# KMO_IO_MV2_8.net
KiCad netlist of a schematic drawn in EAGLE
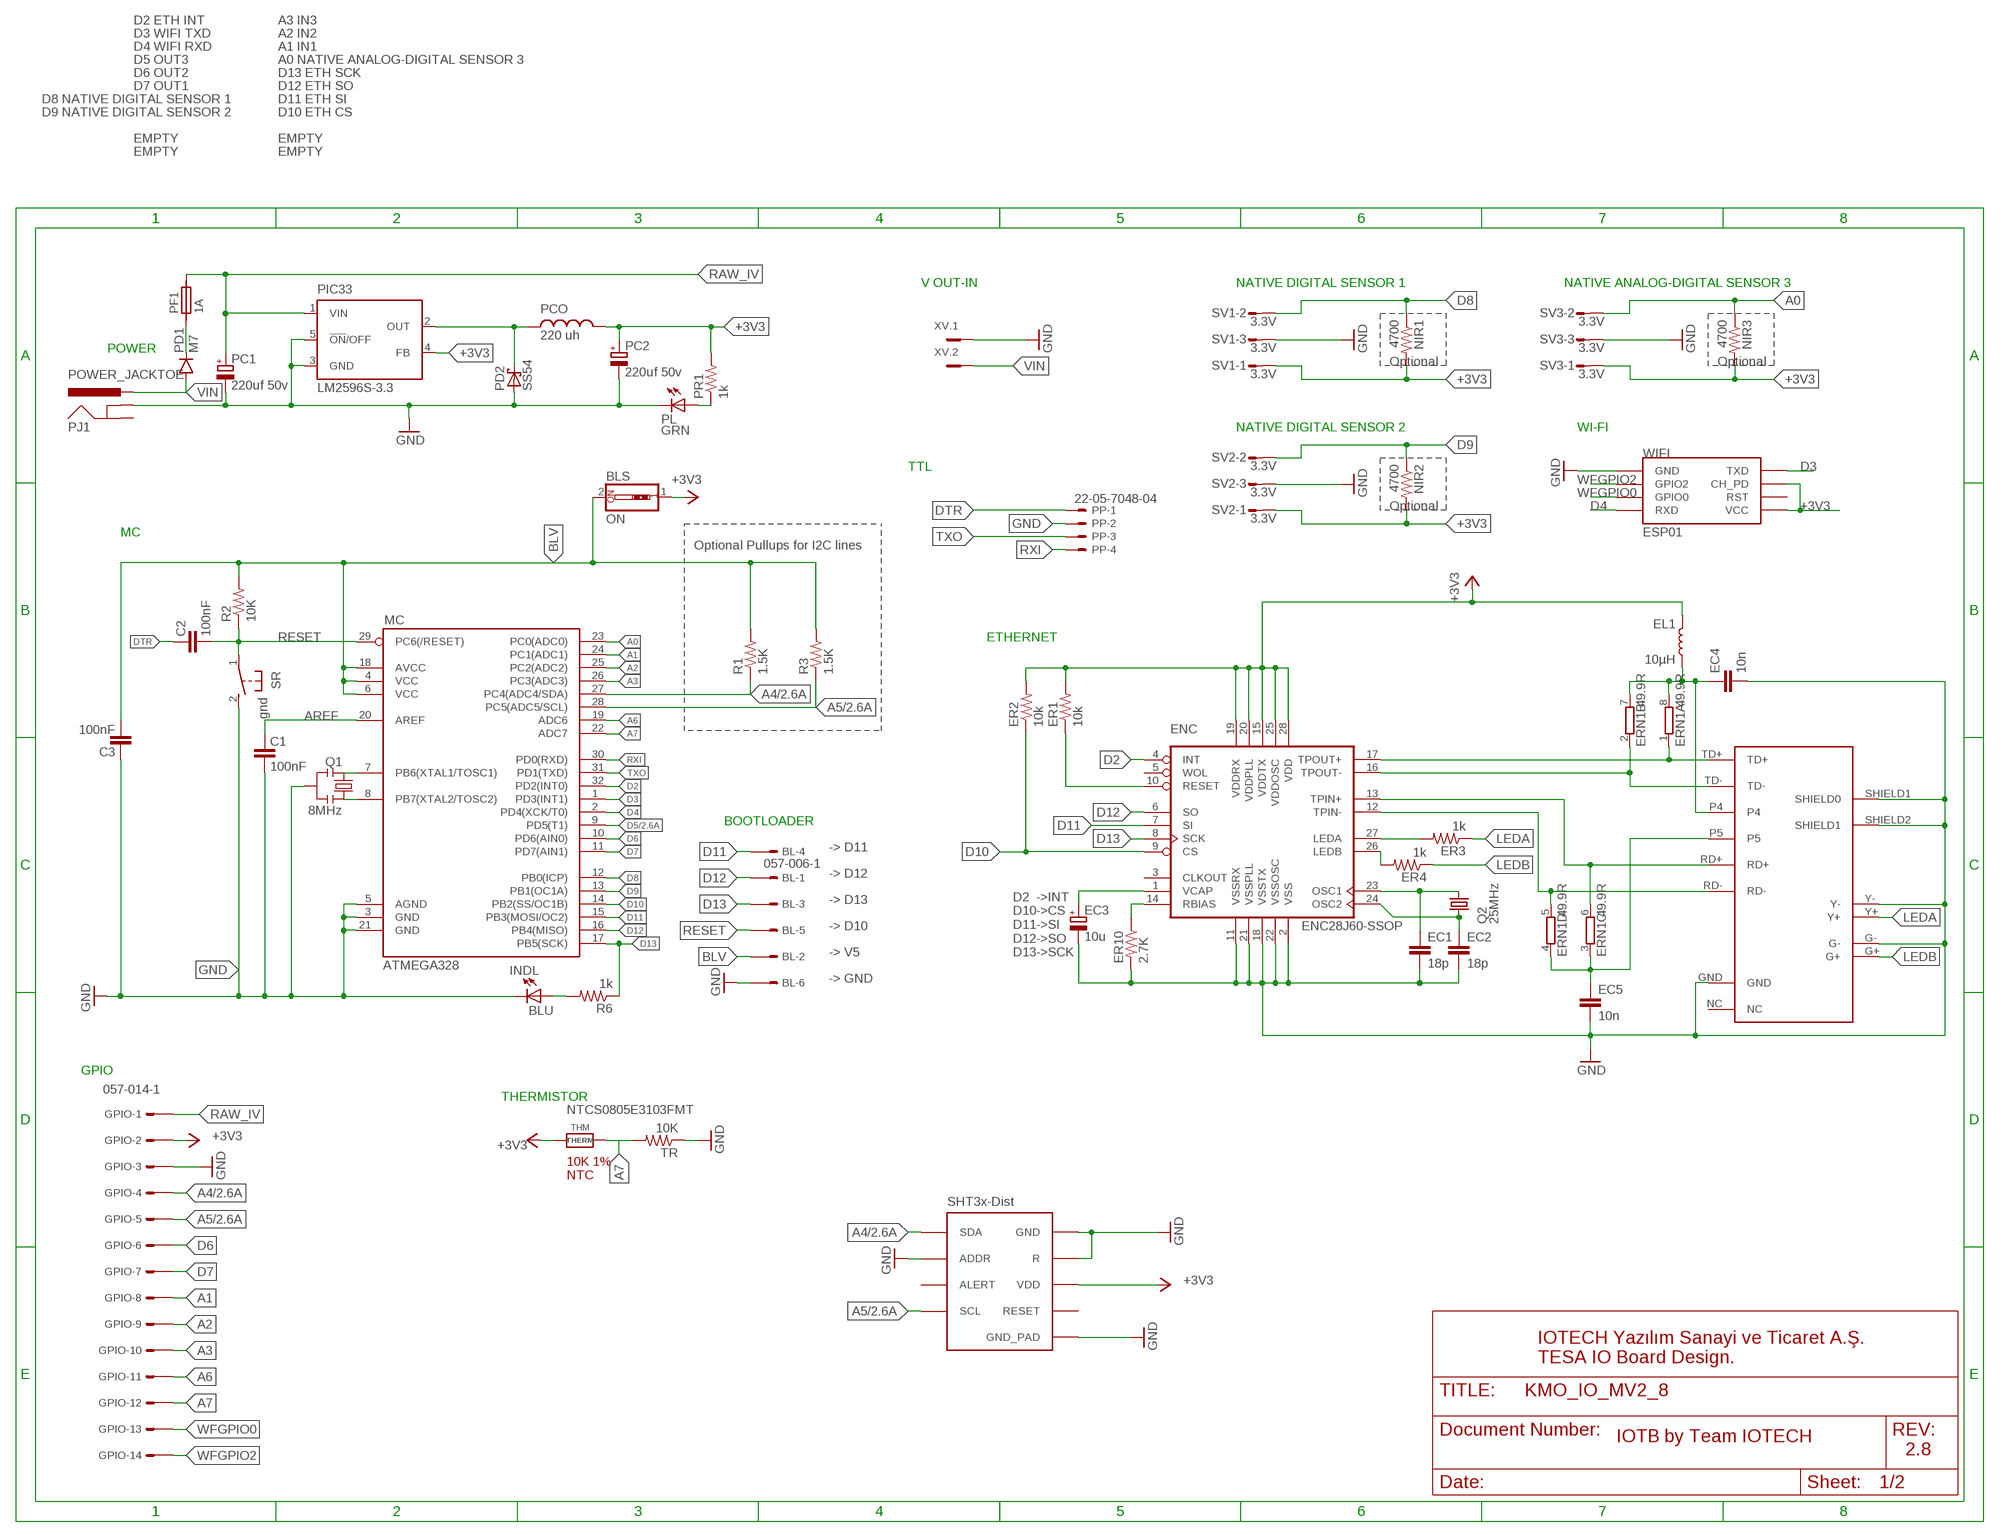
[diagram p0: schematic, sheet 1]
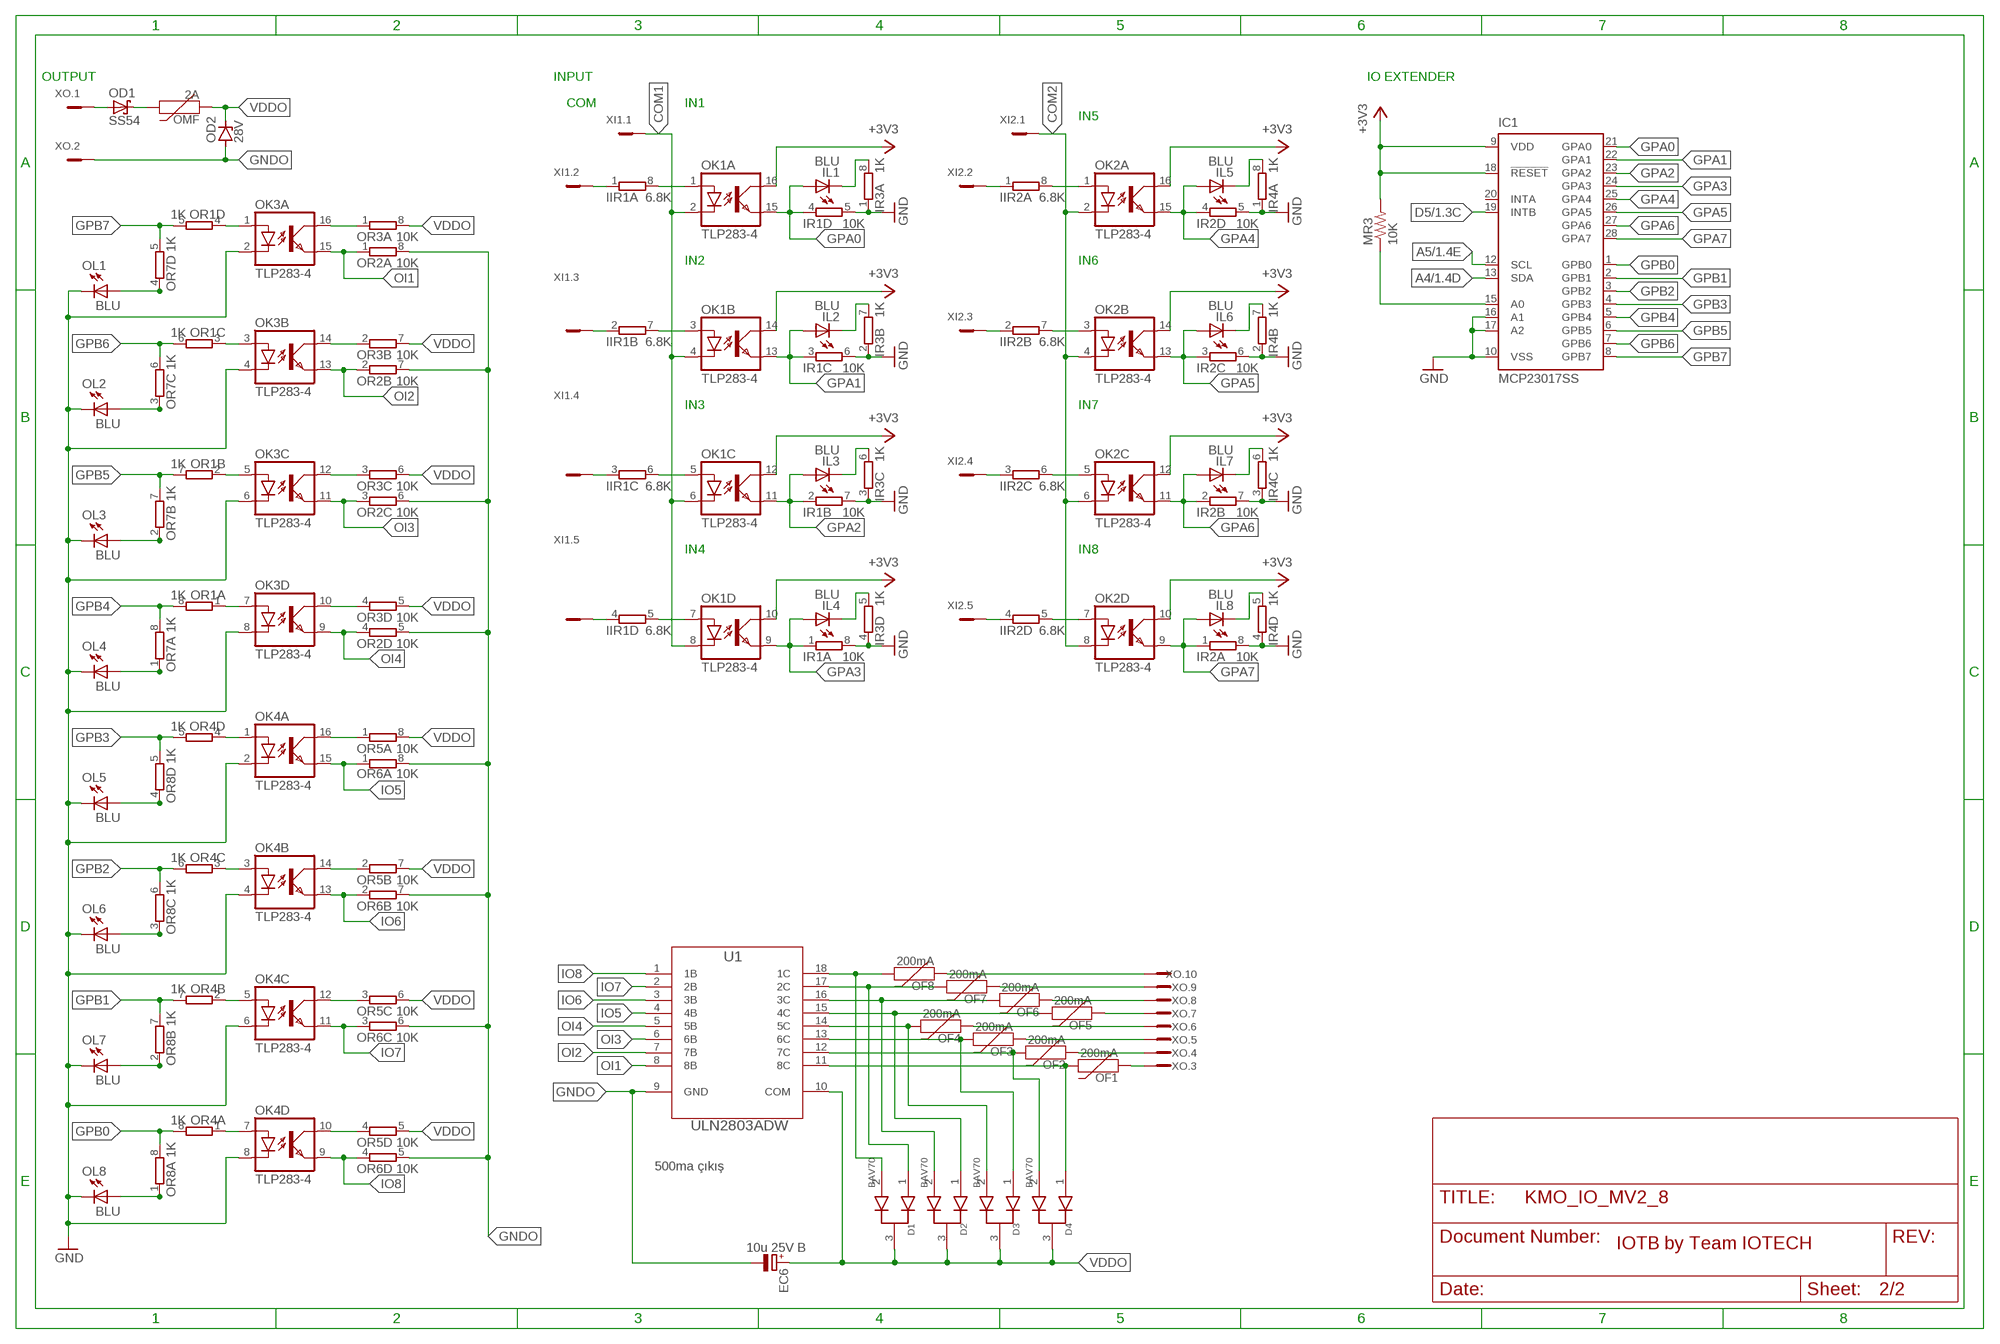
[diagram p1: schematic, sheet 2]

(export (version "E")
  (design (tool "Eeschema 10.0.6"))
  (components
    (comp (ref "D1")
      (value "BAV70")
      (footprint "eagle-import:SOT-23-3")
      (fields (field (name "MF") "Multicomp") (field (name "MP") "BAV70+"))
      (libsource (lib "eagle-import") (part "BAV70"))
    )
    (comp (ref "D2")
      (value "BAV70")
      (footprint "eagle-import:SOT-23-3")
      (fields (field (name "MF") "Multicomp") (field (name "MP") "BAV70+"))
      (libsource (lib "eagle-import") (part "BAV70"))
    )
    (comp (ref "D3")
      (value "BAV70")
      (footprint "eagle-import:SOT-23-3")
      (fields (field (name "MF") "Multicomp") (field (name "MP") "BAV70+"))
      (libsource (lib "eagle-import") (part "BAV70"))
    )
    (comp (ref "D4")
      (value "BAV70")
      (footprint "eagle-import:SOT-23-3")
      (fields (field (name "MF") "Multicomp") (field (name "MP") "BAV70+"))
      (libsource (lib "eagle-import") (part "BAV70"))
    )
    (comp (ref "EC6")
      (value "10u 25V B")
      (footprint "eagle-import:SMC_B")
      (libsource (lib "eagle-import") (part "CPOL-EUSMCB"))
    )
    (comp (ref "IC1")
      (value "MCP23017SS")
      (footprint "eagle-import:SSOP28")
      (fields (field (name "MF") "MICROCHIP") (field (name "MPN") "MCP23017-E/SS"))
      (libsource (lib "eagle-import") (part "MCP23017SS"))
    )
    (comp (ref "IIR1")
      (value "6.8K")
      (footprint "eagle-import:0603-ARV")
      (libsource (lib "eagle-import") (part "4R-N0603-ARV"))
    )
    (comp (ref "IIR2")
      (value "6.8K")
      (footprint "eagle-import:0603-ARV")
      (libsource (lib "eagle-import") (part "4R-N0603-ARV"))
    )
    (comp (ref "IL1")
      (value "BLU")
      (footprint "eagle-import:CHIP-LED0805")
      (libsource (lib "eagle-import") (part "LEDCHIP-LED0805"))
    )
    (comp (ref "IL2")
      (value "BLU")
      (footprint "eagle-import:CHIP-LED0805")
      (libsource (lib "eagle-import") (part "LEDCHIP-LED0805"))
    )
    (comp (ref "IL3")
      (value "BLU")
      (footprint "eagle-import:CHIP-LED0805")
      (libsource (lib "eagle-import") (part "LEDCHIP-LED0805"))
    )
    (comp (ref "IL4")
      (value "BLU")
      (footprint "eagle-import:CHIP-LED0805")
      (libsource (lib "eagle-import") (part "LEDCHIP-LED0805"))
    )
    (comp (ref "IL5")
      (value "BLU")
      (footprint "eagle-import:CHIP-LED0805")
      (libsource (lib "eagle-import") (part "LEDCHIP-LED0805"))
    )
    (comp (ref "IL6")
      (value "BLU")
      (footprint "eagle-import:CHIP-LED0805")
      (libsource (lib "eagle-import") (part "LEDCHIP-LED0805"))
    )
    (comp (ref "IL7")
      (value "BLU")
      (footprint "eagle-import:CHIP-LED0805")
      (libsource (lib "eagle-import") (part "LEDCHIP-LED0805"))
    )
    (comp (ref "IL8")
      (value "BLU")
      (footprint "eagle-import:CHIP-LED0805")
      (libsource (lib "eagle-import") (part "LEDCHIP-LED0805"))
    )
    (comp (ref "IR1")
      (value "10K")
      (footprint "eagle-import:0603-ARV")
      (libsource (lib "eagle-import") (part "4R-N0603-ARV"))
    )
    (comp (ref "IR2")
      (value "10K")
      (footprint "eagle-import:0603-ARV")
      (libsource (lib "eagle-import") (part "4R-N0603-ARV"))
    )
    (comp (ref "IR3")
      (value "1K")
      (footprint "eagle-import:0603-ARV")
      (libsource (lib "eagle-import") (part "4R-N0603-ARV"))
    )
    (comp (ref "IR4")
      (value "1K")
      (footprint "eagle-import:0603-ARV")
      (libsource (lib "eagle-import") (part "4R-N0603-ARV"))
    )
    (comp (ref "MR3")
      (value "10K")
      (footprint "eagle-import:0805")
      (libsource (lib "eagle-import") (part "RESISTOR0805-RES"))
    )
    (comp (ref "OD1")
      (value "SS54")
      (footprint "eagle-import:SMB")
      (libsource (lib "eagle-import") (part "SCHOTTKY-DIODESMD"))
    )
    (comp (ref "OD2")
      (value "28V")
      (footprint "eagle-import:SMB")
      (libsource (lib "eagle-import") (part "ZENER-DIODESMB"))
    )
    (comp (ref "OF1")
      (value "200mA")
      (footprint "eagle-import:1206")
      (libsource (lib "eagle-import") (part "PPTC_0.75A"))
    )
    (comp (ref "OF2")
      (value "200mA")
      (footprint "eagle-import:1206")
      (libsource (lib "eagle-import") (part "PPTC_0.75A"))
    )
    (comp (ref "OF3")
      (value "200mA")
      (footprint "eagle-import:1206")
      (libsource (lib "eagle-import") (part "PPTC_0.75A"))
    )
    (comp (ref "OF4")
      (value "200mA")
      (footprint "eagle-import:1206")
      (libsource (lib "eagle-import") (part "PPTC_0.75A"))
    )
    (comp (ref "OF5")
      (value "200mA")
      (footprint "eagle-import:1206")
      (libsource (lib "eagle-import") (part "PPTC_0.75A"))
    )
    (comp (ref "OF6")
      (value "200mA")
      (footprint "eagle-import:1206")
      (libsource (lib "eagle-import") (part "PPTC_0.75A"))
    )
    (comp (ref "OF7")
      (value "200mA")
      (footprint "eagle-import:1206")
      (libsource (lib "eagle-import") (part "PPTC_0.75A"))
    )
    (comp (ref "OF8")
      (value "200mA")
      (footprint "eagle-import:1206")
      (libsource (lib "eagle-import") (part "PPTC_0.75A"))
    )
    (comp (ref "OK1")
      (value "TLP283-4")
      (footprint "eagle-import:MINI-FLAT-16")
      (fields (field (name "SPICEPREFIX") "O"))
      (libsource (lib "eagle-import") (part "TLP283-4"))
    )
    (comp (ref "OK2")
      (value "TLP283-4")
      (footprint "eagle-import:MINI-FLAT-16")
      (fields (field (name "SPICEPREFIX") "O"))
      (libsource (lib "eagle-import") (part "TLP283-4"))
    )
    (comp (ref "OK3")
      (value "TLP283-4")
      (footprint "eagle-import:MINI-FLAT-16")
      (libsource (lib "eagle-import") (part "TLP283-4"))
    )
    (comp (ref "OK4")
      (value "TLP283-4")
      (footprint "eagle-import:MINI-FLAT-16")
      (libsource (lib "eagle-import") (part "TLP283-4"))
    )
    (comp (ref "OL1")
      (value "BLU")
      (footprint "eagle-import:CHIP-LED0805")
      (libsource (lib "eagle-import") (part "LEDCHIP-LED0805"))
    )
    (comp (ref "OL2")
      (value "BLU")
      (footprint "eagle-import:CHIP-LED0805")
      (libsource (lib "eagle-import") (part "LEDCHIP-LED0805"))
    )
    (comp (ref "OL3")
      (value "BLU")
      (footprint "eagle-import:CHIP-LED0805")
      (libsource (lib "eagle-import") (part "LEDCHIP-LED0805"))
    )
    (comp (ref "OL4")
      (value "BLU")
      (footprint "eagle-import:CHIP-LED0805")
      (libsource (lib "eagle-import") (part "LEDCHIP-LED0805"))
    )
    (comp (ref "OL5")
      (value "BLU")
      (footprint "eagle-import:CHIP-LED0805")
      (libsource (lib "eagle-import") (part "LEDCHIP-LED0805"))
    )
    (comp (ref "OL6")
      (value "BLU")
      (footprint "eagle-import:CHIP-LED0805")
      (libsource (lib "eagle-import") (part "LEDCHIP-LED0805"))
    )
    (comp (ref "OL7")
      (value "BLU")
      (footprint "eagle-import:CHIP-LED0805")
      (libsource (lib "eagle-import") (part "LEDCHIP-LED0805"))
    )
    (comp (ref "OL8")
      (value "BLU")
      (footprint "eagle-import:CHIP-LED0805")
      (libsource (lib "eagle-import") (part "LEDCHIP-LED0805"))
    )
    (comp (ref "OMF")
      (value "2A")
      (footprint "eagle-import:1206")
      (libsource (lib "eagle-import") (part "PPTC_0.75A"))
    )
    (comp (ref "OR1")
      (value "1K")
      (footprint "eagle-import:0603-ARV")
      (libsource (lib "eagle-import") (part "4R-N0603-ARV"))
    )
    (comp (ref "OR2")
      (value "10K")
      (footprint "eagle-import:0603-ARV")
      (libsource (lib "eagle-import") (part "4R-N0603-ARV"))
    )
    (comp (ref "OR3")
      (value "10K")
      (footprint "eagle-import:0603-ARV")
      (libsource (lib "eagle-import") (part "4R-N0603-ARV"))
    )
    (comp (ref "OR4")
      (value "1K")
      (footprint "eagle-import:0603-ARV")
      (libsource (lib "eagle-import") (part "4R-N0603-ARV"))
    )
    (comp (ref "OR5")
      (value "10K")
      (footprint "eagle-import:0603-ARV")
      (libsource (lib "eagle-import") (part "4R-N0603-ARV"))
    )
    (comp (ref "OR6")
      (value "10K")
      (footprint "eagle-import:0603-ARV")
      (libsource (lib "eagle-import") (part "4R-N0603-ARV"))
    )
    (comp (ref "OR7")
      (value "1K")
      (footprint "eagle-import:0603-ARV")
      (libsource (lib "eagle-import") (part "4R-N0603-ARV"))
    )
    (comp (ref "OR8")
      (value "1K")
      (footprint "eagle-import:0603-ARV")
      (libsource (lib "eagle-import") (part "4R-N0603-ARV"))
    )
    (comp (ref "U1")
      (value "ULN2803ADW")
      (footprint "eagle-import:SOIC127P1030X265-18N")
      (libsource (lib "eagle-import") (part "ULN2803ADW"))
    )
    (comp (ref "XI1")
      (value "MC5")
      (footprint "eagle-import:MC5")
      (libsource (lib "eagle-import") (part "MC5"))
    )
    (comp (ref "XI2")
      (value "MC5")
      (footprint "eagle-import:MC5")
      (libsource (lib "eagle-import") (part "MC5"))
    )
    (comp (ref "XO")
      (value "MC10")
      (footprint "eagle-import:MC10")
      (libsource (lib "eagle-import") (part "MC10"))
    )
    (comp (ref "BL")
      (value "057-006-1")
      (footprint "eagle-import:057-006-1")
      (libsource (lib "eagle-import") (part "057-006-1"))
    )
    (comp (ref "BLS")
      (value "ON")
      (footprint "eagle-import:EDG-01")
      (libsource (lib "eagle-import") (part "SW_DIP-1"))
    )
    (comp (ref "C1")
      (value "100nF")
      (footprint "eagle-import:0805")
      (libsource (lib "eagle-import") (part "CAP0805"))
    )
    (comp (ref "C2")
      (value "100nF")
      (footprint "eagle-import:0805")
      (libsource (lib "eagle-import") (part "CAP0805"))
    )
    (comp (ref "C3")
      (value "100nF")
      (footprint "eagle-import:0805")
      (libsource (lib "eagle-import") (part "CAP0805"))
    )
    (comp (ref "EC1")
      (value "18p")
      (footprint "eagle-import:0805")
      (libsource (lib "eagle-import") (part "CAP0805"))
    )
    (comp (ref "EC2")
      (value "18p")
      (footprint "eagle-import:0805")
      (libsource (lib "eagle-import") (part "CAP0805"))
    )
    (comp (ref "EC3")
      (value "10u")
      (footprint "eagle-import:CT3216")
      (libsource (lib "eagle-import") (part "CPOL-EUCT3216"))
    )
    (comp (ref "EC4")
      (value "10n")
      (footprint "eagle-import:0805")
      (libsource (lib "eagle-import") (part "CAP0805"))
    )
    (comp (ref "EC5")
      (value "10n")
      (footprint "eagle-import:0805")
      (libsource (lib "eagle-import") (part "CAP0805"))
    )
    (comp (ref "EL1")
      (value "10µH")
      (footprint "eagle-import:0805")
      (libsource (lib "eagle-import") (part "INDUCTOR-0805-3.3UH"))
    )
    (comp (ref "ENC")
      (value "ENC28J60-SSOP")
      (footprint "eagle-import:SSOP28")
      (libsource (lib "eagle-import") (part "ENC28J60-SSOP"))
    )
    (comp (ref "ER1")
      (value "10k")
      (footprint "eagle-import:0805")
      (libsource (lib "eagle-import") (part "RESISTOR0805-RES"))
    )
    (comp (ref "ER2")
      (value "10k")
      (footprint "eagle-import:0805")
      (libsource (lib "eagle-import") (part "RESISTOR0805-RES"))
    )
    (comp (ref "ER3")
      (value "1k")
      (footprint "eagle-import:0805")
      (libsource (lib "eagle-import") (part "RESISTOR0805-RES"))
    )
    (comp (ref "ER4")
      (value "1k")
      (footprint "eagle-import:0805")
      (libsource (lib "eagle-import") (part "RESISTOR0805-RES"))
    )
    (comp (ref "ER10")
      (value "2.7K")
      (footprint "eagle-import:0805")
      (libsource (lib "eagle-import") (part "RESISTOR0805-RES"))
    )
    (comp (ref "ERN1")
      (value "49.9R")
      (footprint "eagle-import:0603-ARV")
      (libsource (lib "eagle-import") (part "4R-N0603-ARV"))
    )
    (comp (ref "GPIO")
      (value "057-014-1")
      (footprint "eagle-import:057-014-1")
      (libsource (lib "eagle-import") (part "057-014-1"))
    )
    (comp (ref "INDL")
      (value "BLU")
      (footprint "eagle-import:CHIP-LED0805")
      (libsource (lib "eagle-import") (part "LEDCHIP-LED0805"))
    )
    (comp (ref "MC")
      (value "ATMEGA328")
      (footprint "eagle-import:TQFP32-08")
      (libsource (lib "eagle-import") (part "ATMEGA168"))
    )
    (comp (ref "NIR1")
      (value "4700")
      (footprint "eagle-import:0805")
      (libsource (lib "eagle-import") (part "RESISTOR0805-RES"))
    )
    (comp (ref "NIR2")
      (value "4700")
      (footprint "eagle-import:0805")
      (libsource (lib "eagle-import") (part "RESISTOR0805-RES"))
    )
    (comp (ref "NIR3")
      (value "4700")
      (footprint "eagle-import:0805")
      (libsource (lib "eagle-import") (part "RESISTOR0805-RES"))
    )
    (comp (ref "PC1")
      (value "220uf 50v")
      (footprint "eagle-import:140CLH-1010")
      (libsource (lib "eagle-import") (part "CPOL-EU140CLH-1010"))
    )
    (comp (ref "PC2")
      (value "220uf 50v")
      (footprint "eagle-import:140CLH-1010")
      (libsource (lib "eagle-import") (part "CPOL-EU140CLH-1010"))
    )
    (comp (ref "PCO")
      (value "220 uh")
      (footprint "eagle-import:MSS1260")
      (libsource (lib "eagle-import") (part "MSS1260"))
    )
    (comp (ref "PD1")
      (value "M7")
      (footprint "eagle-import:SMA-DIODE")
      (libsource (lib "eagle-import") (part "DIODESMA"))
    )
    (comp (ref "PD2")
      (value "SS54")
      (footprint "eagle-import:SMB")
      (libsource (lib "eagle-import") (part "SCHOTTKY-DIODESMD"))
    )
    (comp (ref "PF1")
      (value "1A")
      (footprint "eagle-import:1820")
      (libsource (lib "eagle-import") (part "SIBA194600"))
    )
    (comp (ref "PIC33")
      (value "LM2596S-3.3")
      (footprint "eagle-import:TO263-5")
      (fields
        (field (name "MF") "NATIONAL SEMICONDUCTOR")
        (field (name "MPN") "LM2596S-ADJ/NOPB")
        (field (name "SPICEPREFIX") "X")
      )
      (libsource (lib "eagle-import") (part "LM2596S"))
    )
    (comp (ref "PJ1")
      (value "POWER_JACKTOE")
      (footprint "eagle-import:POWER_JACK_SMD_OVERPASTE_TOE")
      (libsource (lib "eagle-import") (part "POWER_JACKTOE"))
    )
    (comp (ref "PL")
      (value "GRN")
      (footprint "eagle-import:CHIP-LED0805")
      (libsource (lib "eagle-import") (part "LEDCHIP-LED0805"))
    )
    (comp (ref "PP")
      (value "22-05-7048-04")
      (footprint "eagle-import:7395-04")
      (fields (field (name "MF") "MOLEX"))
      (libsource (lib "eagle-import") (part "22-?-0405-7048"))
    )
    (comp (ref "PR1")
      (value "1k")
      (footprint "eagle-import:0805")
      (libsource (lib "eagle-import") (part "RESISTOR0805-RES"))
    )
    (comp (ref "Q1")
      (value "8MHz")
      (footprint "eagle-import:RESONATOR-SMD-1_1")
      (libsource (lib "eagle-import") (part "RESONATOR1{colon}1"))
    )
    (comp (ref "Q2")
      (value "25MHz")
      (footprint "eagle-import:5.0X3.2_2")
      (libsource (lib "eagle-import") (part "KX-9B"))
    )
    (comp (ref "R1")
      (value "1.5K")
      (footprint "eagle-import:0805")
      (libsource (lib "eagle-import") (part "RESISTOR0805-RES"))
    )
    (comp (ref "R2")
      (value "10K")
      (footprint "eagle-import:0805")
      (libsource (lib "eagle-import") (part "RESISTOR0805-RES"))
    )
    (comp (ref "R3")
      (value "1.5K")
      (footprint "eagle-import:0805")
      (libsource (lib "eagle-import") (part "RESISTOR0805-RES"))
    )
    (comp (ref "R6")
      (value "1k")
      (footprint "eagle-import:0805")
      (libsource (lib "eagle-import") (part "RESISTOR0805-RES"))
    )
    (comp (ref "SHT")
      (value "SHT3X")
      (footprint "eagle-import:SHT3X")
      (libsource (lib "eagle-import") (part "SHT3X"))
    )
    (comp (ref "SR")
      (value "gnd")
      (footprint "eagle-import:B3F-31XX")
      (fields (field (name "MPN") "B3F-3100"))
      (libsource (lib "eagle-import") (part "31-XX"))
    )
    (comp (ref "SV1")
      (value "3.3V")
      (footprint "eagle-import:S03P")
      (libsource (lib "eagle-import") (part "S03P"))
    )
    (comp (ref "SV2")
      (value "3.3V")
      (footprint "eagle-import:S03P")
      (libsource (lib "eagle-import") (part "S03P"))
    )
    (comp (ref "SV3")
      (value "3.3V")
      (footprint "eagle-import:S03P")
      (libsource (lib "eagle-import") (part "S03P"))
    )
    (comp (ref "THM")
      (value "THERM")
      (footprint "eagle-import:MICROBUILDER_0805_NOTHERMALS")
      (libsource (lib "eagle-import") (part "MICROBUILDER_RESISTOR0805_NOTHERMALS"))
    )
    (comp (ref "TR")
      (value "10K")
      (footprint "eagle-import:0805")
      (libsource (lib "eagle-import") (part "RESISTOR0805-RES"))
    )
    (comp (ref "U$2")
      (value "HR911105A")
      (footprint "eagle-import:RJ45")
      (libsource (lib "eagle-import") (part "HR911105A"))
    )
    (comp (ref "WIFI")
      (value "ESP01")
      (footprint "eagle-import:ESP01")
      (libsource (lib "eagle-import") (part "ESP01"))
    )
    (comp (ref "XV")
      (value "MC2")
      (footprint "eagle-import:MC2")
      (libsource (lib "eagle-import") (part "MC2"))
    )
  )
  (nets
    (net (code "1") (name "+3V3") (class "Default")
      (node (ref "BLS") (pin "1") (pinfunction "1_1") (pintype "passive"))
      (node (ref "EL1") (pin "1") (pinfunction "1_1") (pintype "passive"))
      (node (ref "ENC") (pin "15") (pinfunction "VDDTX_15") (pintype "power_in"))
      (node (ref "ENC") (pin "19") (pinfunction "VDDRX_19") (pintype "power_in"))
      (node (ref "ENC") (pin "20") (pinfunction "VDDPLL_20") (pintype "power_in"))
      (node (ref "ENC") (pin "25") (pinfunction "VDDOSC_25") (pintype "power_in"))
      (node (ref "ENC") (pin "28") (pinfunction "VDD_28") (pintype "power_in"))
      (node (ref "ER1") (pin "2") (pinfunction "2_2") (pintype "passive"))
      (node (ref "ER2") (pin "2") (pinfunction "2_2") (pintype "passive"))
      (node (ref "GPIO") (pin "2") (pinfunction "S_2") (pintype "passive"))
      (node (ref "IC1") (pin "18") (pinfunction "~{RESET}_18") (pintype "input"))
      (node (ref "IC1") (pin "9") (pinfunction "VDD_9") (pintype "power_in"))
      (node (ref "MR3") (pin "2") (pinfunction "2_2") (pintype "passive"))
      (node (ref "NIR1") (pin "2") (pinfunction "2_2") (pintype "passive"))
      (node (ref "NIR2") (pin "2") (pinfunction "2_2") (pintype "passive"))
      (node (ref "NIR3") (pin "2") (pinfunction "2_2") (pintype "passive"))
      (node (ref "OK1") (pin "10") (pinfunction "COL_10") (pintype "passive"))
      (node (ref "OK1") (pin "12") (pinfunction "COL_12") (pintype "passive"))
      (node (ref "OK1") (pin "14") (pinfunction "COL_14") (pintype "passive"))
      (node (ref "OK1") (pin "16") (pinfunction "COL_16") (pintype "passive"))
      (node (ref "OK2") (pin "10") (pinfunction "COL_10") (pintype "passive"))
      (node (ref "OK2") (pin "12") (pinfunction "COL_12") (pintype "passive"))
      (node (ref "OK2") (pin "14") (pinfunction "COL_14") (pintype "passive"))
      (node (ref "OK2") (pin "16") (pinfunction "COL_16") (pintype "passive"))
      (node (ref "PC2") (pin "+") (pinfunction "+_+") (pintype "passive"))
      (node (ref "PCO") (pin "P$1") (pinfunction "P$1_P$1") (pintype "passive"))
      (node (ref "PIC33") (pin "4") (pinfunction "FB_4") (pintype "input"))
      (node (ref "PR1") (pin "2") (pinfunction "2_2") (pintype "passive"))
      (node (ref "SHT") (pin "VDD") (pinfunction "VDD_VDD") (pintype "bidirectional"))
      (node (ref "SV1") (pin "1") (pinfunction "S_1") (pintype "passive"))
      (node (ref "SV2") (pin "1") (pinfunction "S_1") (pintype "passive"))
      (node (ref "SV3") (pin "1") (pinfunction "S_1") (pintype "passive"))
      (node (ref "THM") (pin "1") (pinfunction "1_1") (pintype "passive"))
      (node (ref "WIFI") (pin "CH_PD") (pinfunction "CH_PD_CH_PD") (pintype "bidirectional"))
      (node (ref "WIFI") (pin "VCC") (pinfunction "VCC_VCC") (pintype "bidirectional"))
    )
    (net (code "2") (name "A0") (class "Default")
      (node (ref "MC") (pin "23") (pinfunction "PC0(ADC0)_23") (pintype "bidirectional"))
      (node (ref "NIR3") (pin "1") (pinfunction "1_1") (pintype "passive"))
      (node (ref "SV3") (pin "2") (pinfunction "S_2") (pintype "passive"))
    )
    (net (code "3") (name "A1") (class "Default")
      (node (ref "GPIO") (pin "8") (pinfunction "S_8") (pintype "passive"))
      (node (ref "MC") (pin "24") (pinfunction "PC1(ADC1)_24") (pintype "bidirectional"))
    )
    (net (code "4") (name "A2") (class "Default")
      (node (ref "GPIO") (pin "9") (pinfunction "S_9") (pintype "passive"))
      (node (ref "MC") (pin "25") (pinfunction "PC2(ADC2)_25") (pintype "bidirectional"))
    )
    (net (code "5") (name "A3") (class "Default")
      (node (ref "GPIO") (pin "10") (pinfunction "S_10") (pintype "passive"))
      (node (ref "MC") (pin "26") (pinfunction "PC3(ADC3)_26") (pintype "bidirectional"))
    )
    (net (code "6") (name "A4") (class "Default")
      (node (ref "GPIO") (pin "4") (pinfunction "S_4") (pintype "passive"))
      (node (ref "IC1") (pin "13") (pinfunction "SDA_13") (pintype "bidirectional"))
      (node (ref "MC") (pin "27") (pinfunction "PC4(ADC4/SDA)_27") (pintype "bidirectional"))
      (node (ref "R1") (pin "1") (pinfunction "1_1") (pintype "passive"))
      (node (ref "SHT") (pin "SDA") (pinfunction "SDA_SDA") (pintype "bidirectional"))
    )
    (net (code "7") (name "A5") (class "Default")
      (node (ref "GPIO") (pin "5") (pinfunction "S_5") (pintype "passive"))
      (node (ref "IC1") (pin "12") (pinfunction "SCL_12") (pintype "input"))
      (node (ref "MC") (pin "28") (pinfunction "PC5(ADC5/SCL)_28") (pintype "bidirectional"))
      (node (ref "R3") (pin "1") (pinfunction "1_1") (pintype "passive"))
      (node (ref "SHT") (pin "SCL") (pinfunction "SCL_SCL") (pintype "bidirectional"))
    )
    (net (code "8") (name "A6") (class "Default")
      (node (ref "GPIO") (pin "11") (pinfunction "S_11") (pintype "passive"))
      (node (ref "MC") (pin "19") (pinfunction "ADC6_19") (pintype "bidirectional"))
    )
    (net (code "9") (name "A7") (class "Default")
      (node (ref "GPIO") (pin "12") (pinfunction "S_12") (pintype "passive"))
      (node (ref "MC") (pin "22") (pinfunction "ADC7_22") (pintype "bidirectional"))
      (node (ref "THM") (pin "2") (pinfunction "2_2") (pintype "passive"))
      (node (ref "TR") (pin "2") (pinfunction "2_2") (pintype "passive"))
    )
    (net (code "10") (name "AREF") (class "Default")
      (node (ref "C1") (pin "2") (pinfunction "2_2") (pintype "passive"))
      (node (ref "MC") (pin "20") (pinfunction "AREF_20") (pintype "bidirectional"))
    )
    (net (code "11") (name "BLV") (class "Default")
      (node (ref "BL") (pin "2") (pinfunction "S_2") (pintype "passive"))
      (node (ref "BLS") (pin "2") (pinfunction "2_2") (pintype "passive"))
      (node (ref "C3") (pin "1") (pinfunction "1_1") (pintype "passive"))
      (node (ref "MC") (pin "18") (pinfunction "AVCC_18") (pintype "bidirectional"))
      (node (ref "MC") (pin "4") (pinfunction "VCC_4") (pintype "bidirectional"))
      (node (ref "MC") (pin "6") (pinfunction "VCC_6") (pintype "bidirectional"))
      (node (ref "R1") (pin "2") (pinfunction "2_2") (pintype "passive"))
      (node (ref "R2") (pin "2") (pinfunction "2_2") (pintype "passive"))
      (node (ref "R3") (pin "2") (pinfunction "2_2") (pintype "passive"))
    )
    (net (code "12") (name "COM1") (class "Default")
      (node (ref "OK1") (pin "2") (pinfunction "C_2") (pintype "passive"))
      (node (ref "OK1") (pin "4") (pinfunction "C_4") (pintype "passive"))
      (node (ref "OK1") (pin "6") (pinfunction "C_6") (pintype "passive"))
      (node (ref "OK1") (pin "8") (pinfunction "C_8") (pintype "passive"))
      (node (ref "XI1") (pin "1") (pinfunction "SK_1") (pintype "passive"))
    )
    (net (code "13") (name "COM2") (class "Default")
      (node (ref "OK2") (pin "2") (pinfunction "C_2") (pintype "passive"))
      (node (ref "OK2") (pin "4") (pinfunction "C_4") (pintype "passive"))
      (node (ref "OK2") (pin "6") (pinfunction "C_6") (pintype "passive"))
      (node (ref "OK2") (pin "8") (pinfunction "C_8") (pintype "passive"))
      (node (ref "XI2") (pin "1") (pinfunction "SK_1") (pintype "passive"))
    )
    (net (code "14") (name "D2") (class "Default")
      (node (ref "ENC") (pin "4") (pinfunction "INT_4") (pintype "output"))
      (node (ref "MC") (pin "32") (pinfunction "PD2(INT0)_32") (pintype "bidirectional"))
    )
    (net (code "15") (name "D3") (class "Default")
      (node (ref "MC") (pin "1") (pinfunction "PD3(INT1)_1") (pintype "bidirectional"))
      (node (ref "WIFI") (pin "TX") (pinfunction "TXD_TX") (pintype "bidirectional"))
    )
    (net (code "16") (name "D4") (class "Default")
      (node (ref "MC") (pin "2") (pinfunction "PD4(XCK/T0)_2") (pintype "bidirectional"))
      (node (ref "WIFI") (pin "RX") (pinfunction "RXD_RX") (pintype "bidirectional"))
    )
    (net (code "17") (name "D5") (class "Default")
      (node (ref "IC1") (pin "19") (pinfunction "INTB_19") (pintype "output"))
      (node (ref "MC") (pin "9") (pinfunction "PD5(T1)_9") (pintype "bidirectional"))
    )
    (net (code "18") (name "D6") (class "Default")
      (node (ref "GPIO") (pin "6") (pinfunction "S_6") (pintype "passive"))
      (node (ref "MC") (pin "10") (pinfunction "PD6(AIN0)_10") (pintype "bidirectional"))
    )
    (net (code "19") (name "D7") (class "Default")
      (node (ref "GPIO") (pin "7") (pinfunction "S_7") (pintype "passive"))
      (node (ref "MC") (pin "11") (pinfunction "PD7(AIN1)_11") (pintype "bidirectional"))
    )
    (net (code "20") (name "D8") (class "Default")
      (node (ref "MC") (pin "12") (pinfunction "PB0(ICP)_12") (pintype "bidirectional"))
      (node (ref "NIR1") (pin "1") (pinfunction "1_1") (pintype "passive"))
      (node (ref "SV1") (pin "2") (pinfunction "S_2") (pintype "passive"))
    )
    (net (code "21") (name "D9") (class "Default")
      (node (ref "MC") (pin "13") (pinfunction "PB1(OC1A)_13") (pintype "bidirectional"))
      (node (ref "NIR2") (pin "1") (pinfunction "1_1") (pintype "passive"))
      (node (ref "SV2") (pin "2") (pinfunction "S_2") (pintype "passive"))
    )
    (net (code "22") (name "D10") (class "Default")
      (node (ref "ENC") (pin "9") (pinfunction "CS_9") (pintype "input"))
      (node (ref "ER2") (pin "1") (pinfunction "1_1") (pintype "passive"))
      (node (ref "MC") (pin "14") (pinfunction "PB2(SS/OC1B)_14") (pintype "bidirectional"))
    )
    (net (code "23") (name "D11") (class "Default")
      (node (ref "BL") (pin "4") (pinfunction "S_4") (pintype "passive"))
      (node (ref "ENC") (pin "7") (pinfunction "SI_7") (pintype "input"))
      (node (ref "MC") (pin "15") (pinfunction "PB3(MOSI/OC2)_15") (pintype "bidirectional"))
    )
    (net (code "24") (name "D12") (class "Default")
      (node (ref "BL") (pin "1") (pinfunction "S_1") (pintype "passive"))
      (node (ref "ENC") (pin "6") (pinfunction "SO_6") (pintype "output"))
      (node (ref "MC") (pin "16") (pinfunction "PB4(MISO)_16") (pintype "bidirectional"))
    )
    (net (code "25") (name "D13") (class "Default")
      (node (ref "BL") (pin "3") (pinfunction "S_3") (pintype "passive"))
      (node (ref "ENC") (pin "8") (pinfunction "SCK_8") (pintype "input"))
      (node (ref "MC") (pin "17") (pinfunction "PB5(SCK)_17") (pintype "bidirectional"))
      (node (ref "R6") (pin "1") (pinfunction "1_1") (pintype "passive"))
    )
    (net (code "26") (name "DTR") (class "Default")
      (node (ref "C2") (pin "2") (pinfunction "2_2") (pintype "passive"))
      (node (ref "PP") (pin "1") (pinfunction "S_1") (pintype "passive"))
    )
    (net (code "27") (name "GND") (class "Default")
      (node (ref "BL") (pin "6") (pinfunction "S_6") (pintype "passive"))
      (node (ref "C1") (pin "1") (pinfunction "1_1") (pintype "passive"))
      (node (ref "C3") (pin "2") (pinfunction "2_2") (pintype "passive"))
      (node (ref "EC1") (pin "2") (pinfunction "2_2") (pintype "passive"))
      (node (ref "EC2") (pin "2") (pinfunction "2_2") (pintype "passive"))
      (node (ref "EC3") (pin "-") (pinfunction "-_-") (pintype "passive"))
      (node (ref "EC4") (pin "2") (pinfunction "2_2") (pintype "passive"))
      (node (ref "EC5") (pin "2") (pinfunction "2_2") (pintype "passive"))
      (node (ref "ENC") (pin "11") (pinfunction "VSSRX_11") (pintype "power_in"))
      (node (ref "ENC") (pin "18") (pinfunction "VSSTX_18") (pintype "power_in"))
      (node (ref "ENC") (pin "2") (pinfunction "VSS_2") (pintype "power_in"))
      (node (ref "ENC") (pin "21") (pinfunction "VSSPLL_21") (pintype "power_in"))
      (node (ref "ENC") (pin "22") (pinfunction "VSSOSC_22") (pintype "power_in"))
      (node (ref "ER10") (pin "2") (pinfunction "2_2") (pintype "passive"))
      (node (ref "GPIO") (pin "3") (pinfunction "S_3") (pintype "passive"))
      (node (ref "IC1") (pin "10") (pinfunction "VSS_10") (pintype "power_in"))
      (node (ref "IC1") (pin "16") (pinfunction "A1_16") (pintype "input"))
      (node (ref "IC1") (pin "17") (pinfunction "A2_17") (pintype "input"))
      (node (ref "INDL") (pin "C") (pinfunction "C_C") (pintype "passive"))
      (node (ref "IR1") (pin "5") (pinfunction "2_5") (pintype "passive"))
      (node (ref "IR1") (pin "6") (pinfunction "2_6") (pintype "passive"))
      (node (ref "IR1") (pin "7") (pinfunction "2_7") (pintype "passive"))
      (node (ref "IR1") (pin "8") (pinfunction "2_8") (pintype "passive"))
      (node (ref "IR2") (pin "5") (pinfunction "2_5") (pintype "passive"))
      (node (ref "IR2") (pin "6") (pinfunction "2_6") (pintype "passive"))
      (node (ref "IR2") (pin "7") (pinfunction "2_7") (pintype "passive"))
      (node (ref "IR2") (pin "8") (pinfunction "2_8") (pintype "passive"))
      (node (ref "IR3") (pin "1") (pinfunction "1_1") (pintype "passive"))
      (node (ref "IR3") (pin "2") (pinfunction "1_2") (pintype "passive"))
      (node (ref "IR3") (pin "3") (pinfunction "1_3") (pintype "passive"))
      (node (ref "IR3") (pin "4") (pinfunction "1_4") (pintype "passive"))
      (node (ref "IR4") (pin "1") (pinfunction "1_1") (pintype "passive"))
      (node (ref "IR4") (pin "2") (pinfunction "1_2") (pintype "passive"))
      (node (ref "IR4") (pin "3") (pinfunction "1_3") (pintype "passive"))
      (node (ref "IR4") (pin "4") (pinfunction "1_4") (pintype "passive"))
      (node (ref "MC") (pin "21") (pinfunction "GND_21") (pintype "bidirectional"))
      (node (ref "MC") (pin "3") (pinfunction "GND_3") (pintype "bidirectional"))
      (node (ref "MC") (pin "5") (pinfunction "AGND_5") (pintype "bidirectional"))
      (node (ref "OK3") (pin "2") (pinfunction "C_2") (pintype "passive"))
      (node (ref "OK3") (pin "4") (pinfunction "C_4") (pintype "passive"))
      (node (ref "OK3") (pin "6") (pinfunction "C_6") (pintype "passive"))
      (node (ref "OK3") (pin "8") (pinfunction "C_8") (pintype "passive"))
      (node (ref "OK4") (pin "2") (pinfunction "C_2") (pintype "passive"))
      (node (ref "OK4") (pin "4") (pinfunction "C_4") (pintype "passive"))
      (node (ref "OK4") (pin "6") (pinfunction "C_6") (pintype "passive"))
      (node (ref "OK4") (pin "8") (pinfunction "C_8") (pintype "passive"))
      (node (ref "OL1") (pin "C") (pinfunction "C_C") (pintype "passive"))
      (node (ref "OL2") (pin "C") (pinfunction "C_C") (pintype "passive"))
      (node (ref "OL3") (pin "C") (pinfunction "C_C") (pintype "passive"))
      (node (ref "OL4") (pin "C") (pinfunction "C_C") (pintype "passive"))
      (node (ref "OL5") (pin "C") (pinfunction "C_C") (pintype "passive"))
      (node (ref "OL6") (pin "C") (pinfunction "C_C") (pintype "passive"))
      (node (ref "OL7") (pin "C") (pinfunction "C_C") (pintype "passive"))
      (node (ref "OL8") (pin "C") (pinfunction "C_C") (pintype "passive"))
      (node (ref "PC1") (pin "-") (pinfunction "-_-") (pintype "passive"))
      (node (ref "PC2") (pin "-") (pinfunction "-_-") (pintype "passive"))
      (node (ref "PD2") (pin "A") (pinfunction "A_A") (pintype "passive"))
      (node (ref "PIC33") (pin "3") (pinfunction "GND_3") (pintype "power_in"))
      (node (ref "PIC33") (pin "5") (pinfunction "~{ON}/OFF_5") (pintype "input"))
      (node (ref "PJ1") (pin "GND") (pinfunction "GNDBREAK_GND") (pintype "bidirectional"))
      (node (ref "PL") (pin "C") (pinfunction "C_C") (pintype "passive"))
      (node (ref "PP") (pin "2") (pinfunction "S_2") (pintype "passive"))
      (node (ref "Q1") (pin "2") (pinfunction "2_2") (pintype "passive"))
      (node (ref "SHT") (pin "ADDR") (pinfunction "ADDR_ADDR") (pintype "bidirectional"))
      (node (ref "SHT") (pin "GND") (pinfunction "GND_GND") (pintype "bidirectional"))
      (node (ref "SHT") (pin "GND_PAD") (pinfunction "GND_PAD_GND_PAD") (pintype "bidirectional"))
      (node (ref "SHT") (pin "R") (pinfunction "R_R") (pintype "bidirectional"))
      (node (ref "SR") (pin "2") (pinfunction "S_2") (pintype "passive"))
      (node (ref "SV1") (pin "3") (pinfunction "S_3") (pintype "passive"))
      (node (ref "SV2") (pin "3") (pinfunction "S_3") (pintype "passive"))
      (node (ref "SV3") (pin "3") (pinfunction "S_3") (pintype "passive"))
      (node (ref "TR") (pin "1") (pinfunction "1_1") (pintype "passive"))
      (node (ref "U$2") (pin "G-") (pinfunction "G-_G-") (pintype "bidirectional"))
      (node (ref "U$2") (pin "GND") (pinfunction "GND_GND") (pintype "bidirectional"))
      (node (ref "U$2") (pin "SHIELD1") (pinfunction "SHIELD0_SHIELD1") (pintype "bidirectional"))
      (node (ref "U$2") (pin "SHIELD2") (pinfunction "SHIELD1_SHIELD2") (pintype "bidirectional"))
      (node (ref "U$2") (pin "Y-") (pinfunction "Y-_Y-") (pintype "bidirectional"))
      (node (ref "WIFI") (pin "GND") (pinfunction "GND_GND") (pintype "bidirectional"))
      (node (ref "XV") (pin "1") (pinfunction "SK_1") (pintype "passive"))
    )
    (net (code "28") (name "GNDO") (class "Default")
      (node (ref "EC6") (pin "-") (pinfunction "-_-") (pintype "passive"))
      (node (ref "OD2") (pin "A") (pinfunction "A_A") (pintype "passive"))
      (node (ref "OR2") (pin "5") (pinfunction "2_5") (pintype "passive"))
      (node (ref "OR2") (pin "6") (pinfunction "2_6") (pintype "passive"))
      (node (ref "OR2") (pin "7") (pinfunction "2_7") (pintype "passive"))
      (node (ref "OR2") (pin "8") (pinfunction "2_8") (pintype "passive"))
      (node (ref "OR6") (pin "5") (pinfunction "2_5") (pintype "passive"))
      (node (ref "OR6") (pin "6") (pinfunction "2_6") (pintype "passive"))
      (node (ref "OR6") (pin "7") (pinfunction "2_7") (pintype "passive"))
      (node (ref "OR6") (pin "8") (pinfunction "2_8") (pintype "passive"))
      (node (ref "U1") (pin "9") (pinfunction "GND_9") (pintype "passive"))
      (node (ref "XO") (pin "2") (pinfunction "SK_2") (pintype "passive"))
    )
    (net (code "29") (name "GPA0") (class "Default")
      (node (ref "IC1") (pin "21") (pinfunction "GPA0_21") (pintype "bidirectional"))
      (node (ref "IL1") (pin "A") (pinfunction "A_A") (pintype "passive"))
      (node (ref "IR1") (pin "4") (pinfunction "1_4") (pintype "passive"))
      (node (ref "OK1") (pin "15") (pinfunction "EMIT_15") (pintype "passive"))
    )
    (net (code "30") (name "GPA1") (class "Default")
      (node (ref "IC1") (pin "22") (pinfunction "GPA1_22") (pintype "bidirectional"))
      (node (ref "IL2") (pin "A") (pinfunction "A_A") (pintype "passive"))
      (node (ref "IR1") (pin "3") (pinfunction "1_3") (pintype "passive"))
      (node (ref "OK1") (pin "13") (pinfunction "EMIT_13") (pintype "passive"))
    )
    (net (code "31") (name "GPA2") (class "Default")
      (node (ref "IC1") (pin "23") (pinfunction "GPA2_23") (pintype "bidirectional"))
      (node (ref "IL3") (pin "A") (pinfunction "A_A") (pintype "passive"))
      (node (ref "IR1") (pin "2") (pinfunction "1_2") (pintype "passive"))
      (node (ref "OK1") (pin "11") (pinfunction "EMIT_11") (pintype "passive"))
    )
    (net (code "32") (name "GPA3") (class "Default")
      (node (ref "IC1") (pin "24") (pinfunction "GPA3_24") (pintype "bidirectional"))
      (node (ref "IL4") (pin "A") (pinfunction "A_A") (pintype "passive"))
      (node (ref "IR1") (pin "1") (pinfunction "1_1") (pintype "passive"))
      (node (ref "OK1") (pin "9") (pinfunction "EMIT_9") (pintype "passive"))
    )
    (net (code "33") (name "GPA4") (class "Default")
      (node (ref "IC1") (pin "25") (pinfunction "GPA4_25") (pintype "bidirectional"))
      (node (ref "IL5") (pin "A") (pinfunction "A_A") (pintype "passive"))
      (node (ref "IR2") (pin "4") (pinfunction "1_4") (pintype "passive"))
      (node (ref "OK2") (pin "15") (pinfunction "EMIT_15") (pintype "passive"))
    )
    (net (code "34") (name "GPA5") (class "Default")
      (node (ref "IC1") (pin "26") (pinfunction "GPA5_26") (pintype "bidirectional"))
      (node (ref "IL6") (pin "A") (pinfunction "A_A") (pintype "passive"))
      (node (ref "IR2") (pin "3") (pinfunction "1_3") (pintype "passive"))
      (node (ref "OK2") (pin "13") (pinfunction "EMIT_13") (pintype "passive"))
    )
    (net (code "35") (name "GPA6") (class "Default")
      (node (ref "IC1") (pin "27") (pinfunction "GPA6_27") (pintype "bidirectional"))
      (node (ref "IL7") (pin "A") (pinfunction "A_A") (pintype "passive"))
      (node (ref "IR2") (pin "2") (pinfunction "1_2") (pintype "passive"))
      (node (ref "OK2") (pin "11") (pinfunction "EMIT_11") (pintype "passive"))
    )
    (net (code "36") (name "GPA7") (class "Default")
      (node (ref "IC1") (pin "28") (pinfunction "GPA7_28") (pintype "bidirectional"))
      (node (ref "IL8") (pin "A") (pinfunction "A_A") (pintype "passive"))
      (node (ref "IR2") (pin "1") (pinfunction "1_1") (pintype "passive"))
      (node (ref "OK2") (pin "9") (pinfunction "EMIT_9") (pintype "passive"))
    )
    (net (code "37") (name "GPB0") (class "Default")
      (node (ref "IC1") (pin "1") (pinfunction "GPB0_1") (pintype "bidirectional"))
      (node (ref "OR4") (pin "8") (pinfunction "2_8") (pintype "passive"))
      (node (ref "OR8") (pin "8") (pinfunction "2_8") (pintype "passive"))
    )
    (net (code "38") (name "GPB1") (class "Default")
      (node (ref "IC1") (pin "2") (pinfunction "GPB1_2") (pintype "bidirectional"))
      (node (ref "OR4") (pin "7") (pinfunction "2_7") (pintype "passive"))
      (node (ref "OR8") (pin "7") (pinfunction "2_7") (pintype "passive"))
    )
    (net (code "39") (name "GPB2") (class "Default")
      (node (ref "IC1") (pin "3") (pinfunction "GPB2_3") (pintype "bidirectional"))
      (node (ref "OR4") (pin "6") (pinfunction "2_6") (pintype "passive"))
      (node (ref "OR8") (pin "6") (pinfunction "2_6") (pintype "passive"))
    )
    (net (code "40") (name "GPB3") (class "Default")
      (node (ref "IC1") (pin "4") (pinfunction "GPB3_4") (pintype "bidirectional"))
      (node (ref "OR4") (pin "5") (pinfunction "2_5") (pintype "passive"))
      (node (ref "OR8") (pin "5") (pinfunction "2_5") (pintype "passive"))
    )
    (net (code "41") (name "GPB4") (class "Default")
      (node (ref "IC1") (pin "5") (pinfunction "GPB4_5") (pintype "bidirectional"))
      (node (ref "OR1") (pin "8") (pinfunction "2_8") (pintype "passive"))
      (node (ref "OR7") (pin "8") (pinfunction "2_8") (pintype "passive"))
    )
    (net (code "42") (name "GPB5") (class "Default")
      (node (ref "IC1") (pin "6") (pinfunction "GPB5_6") (pintype "bidirectional"))
      (node (ref "OR1") (pin "7") (pinfunction "2_7") (pintype "passive"))
      (node (ref "OR7") (pin "7") (pinfunction "2_7") (pintype "passive"))
    )
    (net (code "43") (name "GPB6") (class "Default")
      (node (ref "IC1") (pin "7") (pinfunction "GPB6_7") (pintype "bidirectional"))
      (node (ref "OR1") (pin "6") (pinfunction "2_6") (pintype "passive"))
      (node (ref "OR7") (pin "6") (pinfunction "2_6") (pintype "passive"))
    )
    (net (code "44") (name "GPB7") (class "Default")
      (node (ref "IC1") (pin "8") (pinfunction "GPB7_8") (pintype "bidirectional"))
      (node (ref "OR1") (pin "5") (pinfunction "2_5") (pintype "passive"))
      (node (ref "OR7") (pin "5") (pinfunction "2_5") (pintype "passive"))
    )
    (net (code "45") (name "IO5") (class "Default")
      (node (ref "OK4") (pin "15") (pinfunction "EMIT_15") (pintype "passive"))
      (node (ref "OR6") (pin "1") (pinfunction "1_1") (pintype "passive"))
      (node (ref "U1") (pin "4") (pinfunction "4B_4") (pintype "input"))
    )
    (net (code "46") (name "IO6") (class "Default")
      (node (ref "OK4") (pin "13") (pinfunction "EMIT_13") (pintype "passive"))
      (node (ref "OR6") (pin "2") (pinfunction "1_2") (pintype "passive"))
      (node (ref "U1") (pin "3") (pinfunction "3B_3") (pintype "input"))
    )
    (net (code "47") (name "IO7") (class "Default")
      (node (ref "OK4") (pin "11") (pinfunction "EMIT_11") (pintype "passive"))
      (node (ref "OR6") (pin "3") (pinfunction "1_3") (pintype "passive"))
      (node (ref "U1") (pin "2") (pinfunction "2B_2") (pintype "input"))
    )
    (net (code "48") (name "IO8") (class "Default")
      (node (ref "OK4") (pin "9") (pinfunction "EMIT_9") (pintype "passive"))
      (node (ref "OR6") (pin "4") (pinfunction "1_4") (pintype "passive"))
      (node (ref "U1") (pin "1") (pinfunction "1B_1") (pintype "input"))
    )
    (net (code "49") (name "LEDA") (class "Default")
      (node (ref "ER3") (pin "1") (pinfunction "1_1") (pintype "passive"))
      (node (ref "U$2") (pin "Y+") (pinfunction "Y+_Y+") (pintype "bidirectional"))
    )
    (net (code "50") (name "LEDB") (class "Default")
      (node (ref "ER4") (pin "1") (pinfunction "1_1") (pintype "passive"))
      (node (ref "U$2") (pin "G+") (pinfunction "G+_G+") (pintype "bidirectional"))
    )
    (net (code "51") (name "Net-(ENC-LEDA)") (class "Default")
      (node (ref "ENC") (pin "27") (pinfunction "LEDA_27") (pintype "output"))
      (node (ref "ER3") (pin "2") (pinfunction "2_2") (pintype "passive"))
    )
    (net (code "52") (name "Net-(ENC-LEDB)") (class "Default")
      (node (ref "ENC") (pin "26") (pinfunction "LEDB_26") (pintype "output"))
      (node (ref "ER4") (pin "2") (pinfunction "2_2") (pintype "passive"))
    )
    (net (code "53") (name "Net-(ENC-OSC1)") (class "Default")
      (node (ref "EC1") (pin "1") (pinfunction "1_1") (pintype "passive"))
      (node (ref "ENC") (pin "23") (pinfunction "OSC1_23") (pintype "input"))
      (node (ref "Q2") (pin "2") (pinfunction "2_2") (pintype "passive"))
    )
    (net (code "54") (name "Net-(ENC-OSC2)") (class "Default")
      (node (ref "EC2") (pin "1") (pinfunction "1_1") (pintype "passive"))
      (node (ref "ENC") (pin "24") (pinfunction "OSC2_24") (pintype "output"))
      (node (ref "Q2") (pin "1") (pinfunction "1_1") (pintype "passive"))
    )
    (net (code "55") (name "Net-(ENC-RBIAS)") (class "Default")
      (node (ref "ENC") (pin "14") (pinfunction "RBIAS_14") (pintype "passive"))
      (node (ref "ER10") (pin "1") (pinfunction "1_1") (pintype "passive"))
    )
    (net (code "56") (name "Net-(ENC-RESET)") (class "Default")
      (node (ref "ENC") (pin "10") (pinfunction "RESET_10") (pintype "input"))
      (node (ref "ER1") (pin "1") (pinfunction "1_1") (pintype "passive"))
    )
    (net (code "57") (name "Net-(ENC-TPIN+)") (class "Default")
      (node (ref "ENC") (pin "13") (pinfunction "TPIN+_13") (pintype "input"))
      (node (ref "ERN1") (pin "6") (pinfunction "2_6") (pintype "passive"))
      (node (ref "U$2") (pin "RD+") (pinfunction "RD+_RD+") (pintype "bidirectional"))
    )
    (net (code "58") (name "Net-(ENC-TPIN-)") (class "Default")
      (node (ref "ENC") (pin "12") (pinfunction "TPIN-_12") (pintype "input"))
      (node (ref "ERN1") (pin "5") (pinfunction "2_5") (pintype "passive"))
      (node (ref "U$2") (pin "RD-") (pinfunction "RD-_RD-") (pintype "bidirectional"))
    )
    (net (code "59") (name "Net-(ENC-TPOUT+)") (class "Default")
      (node (ref "ENC") (pin "17") (pinfunction "TPOUT+_17") (pintype "output"))
      (node (ref "ERN1") (pin "1") (pinfunction "1_1") (pintype "passive"))
      (node (ref "U$2") (pin "TD+") (pinfunction "TD+_TD+") (pintype "bidirectional"))
    )
    (net (code "60") (name "Net-(ENC-TPOUT-)") (class "Default")
      (node (ref "ENC") (pin "16") (pinfunction "TPOUT-_16") (pintype "output"))
      (node (ref "ERN1") (pin "2") (pinfunction "1_2") (pintype "passive"))
      (node (ref "U$2") (pin "TD-") (pinfunction "TD-_TD-") (pintype "bidirectional"))
    )
    (net (code "61") (name "Net-(ENC-VCAP)") (class "Default")
      (node (ref "EC3") (pin "+") (pinfunction "+_+") (pintype "passive"))
      (node (ref "ENC") (pin "1") (pinfunction "VCAP_1") (pintype "power_in"))
    )
    (net (code "62") (name "Net-(ERN1A-2)") (class "Default")
      (node (ref "EC4") (pin "1") (pinfunction "1_1") (pintype "passive"))
      (node (ref "EL1") (pin "2") (pinfunction "2_2") (pintype "passive"))
      (node (ref "ERN1") (pin "7") (pinfunction "2_7") (pintype "passive"))
      (node (ref "ERN1") (pin "8") (pinfunction "2_8") (pintype "passive"))
      (node (ref "U$2") (pin "P4") (pinfunction "P4_P4") (pintype "bidirectional"))
    )
    (net (code "63") (name "Net-(ERN1C-1)") (class "Default")
      (node (ref "EC5") (pin "1") (pinfunction "1_1") (pintype "passive"))
      (node (ref "ERN1") (pin "3") (pinfunction "1_3") (pintype "passive"))
      (node (ref "ERN1") (pin "4") (pinfunction "1_4") (pintype "passive"))
      (node (ref "U$2") (pin "P5") (pinfunction "P5_P5") (pintype "bidirectional"))
    )
    (net (code "64") (name "Net-(IC1-A0)") (class "Default")
      (node (ref "IC1") (pin "15") (pinfunction "A0_15") (pintype "input"))
      (node (ref "MR3") (pin "1") (pinfunction "1_1") (pintype "passive"))
    )
    (net (code "65") (name "Net-(IIR1A-2)") (class "Default")
      (node (ref "IIR1") (pin "8") (pinfunction "2_8") (pintype "passive"))
      (node (ref "OK1") (pin "1") (pinfunction "A_1") (pintype "passive"))
    )
    (net (code "66") (name "Net-(IIR1B-1)") (class "Default")
      (node (ref "IIR1") (pin "2") (pinfunction "1_2") (pintype "passive"))
      (node (ref "XI1") (pin "3") (pinfunction "SK_3") (pintype "passive"))
    )
    (net (code "67") (name "Net-(IIR1B-2)") (class "Default")
      (node (ref "IIR1") (pin "7") (pinfunction "2_7") (pintype "passive"))
      (node (ref "OK1") (pin "3") (pinfunction "A_3") (pintype "passive"))
    )
    (net (code "68") (name "Net-(IIR1C-1)") (class "Default")
      (node (ref "IIR1") (pin "3") (pinfunction "1_3") (pintype "passive"))
      (node (ref "XI1") (pin "4") (pinfunction "SK_4") (pintype "passive"))
    )
    (net (code "69") (name "Net-(IIR1C-2)") (class "Default")
      (node (ref "IIR1") (pin "6") (pinfunction "2_6") (pintype "passive"))
      (node (ref "OK1") (pin "5") (pinfunction "A_5") (pintype "passive"))
    )
    (net (code "70") (name "Net-(IIR1D-1)") (class "Default")
      (node (ref "IIR1") (pin "4") (pinfunction "1_4") (pintype "passive"))
      (node (ref "XI1") (pin "5") (pinfunction "SK_5") (pintype "passive"))
    )
    (net (code "71") (name "Net-(IIR1D-2)") (class "Default")
      (node (ref "IIR1") (pin "5") (pinfunction "2_5") (pintype "passive"))
      (node (ref "OK1") (pin "7") (pinfunction "A_7") (pintype "passive"))
    )
    (net (code "72") (name "Net-(IIR2A-2)") (class "Default")
      (node (ref "IIR2") (pin "8") (pinfunction "2_8") (pintype "passive"))
      (node (ref "OK2") (pin "1") (pinfunction "A_1") (pintype "passive"))
    )
    (net (code "73") (name "Net-(IIR2B-1)") (class "Default")
      (node (ref "IIR2") (pin "2") (pinfunction "1_2") (pintype "passive"))
      (node (ref "XI2") (pin "3") (pinfunction "SK_3") (pintype "passive"))
    )
    (net (code "74") (name "Net-(IIR2B-2)") (class "Default")
      (node (ref "IIR2") (pin "7") (pinfunction "2_7") (pintype "passive"))
      (node (ref "OK2") (pin "3") (pinfunction "A_3") (pintype "passive"))
    )
    (net (code "75") (name "Net-(IIR2C-1)") (class "Default")
      (node (ref "IIR2") (pin "3") (pinfunction "1_3") (pintype "passive"))
      (node (ref "XI2") (pin "4") (pinfunction "SK_4") (pintype "passive"))
    )
    (net (code "76") (name "Net-(IIR2C-2)") (class "Default")
      (node (ref "IIR2") (pin "6") (pinfunction "2_6") (pintype "passive"))
      (node (ref "OK2") (pin "5") (pinfunction "A_5") (pintype "passive"))
    )
    (net (code "77") (name "Net-(IIR2D-1)") (class "Default")
      (node (ref "IIR2") (pin "4") (pinfunction "1_4") (pintype "passive"))
      (node (ref "XI2") (pin "5") (pinfunction "SK_5") (pintype "passive"))
    )
    (net (code "78") (name "Net-(IIR2D-2)") (class "Default")
      (node (ref "IIR2") (pin "5") (pinfunction "2_5") (pintype "passive"))
      (node (ref "OK2") (pin "7") (pinfunction "A_7") (pintype "passive"))
    )
    (net (code "79") (name "Net-(INDL-PadA)") (class "Default")
      (node (ref "INDL") (pin "A") (pinfunction "A_A") (pintype "passive"))
      (node (ref "R6") (pin "2") (pinfunction "2_2") (pintype "passive"))
    )
    (net (code "80") (name "Net-(IR3A-2)") (class "Default")
      (node (ref "IL1") (pin "C") (pinfunction "C_C") (pintype "passive"))
      (node (ref "IR3") (pin "8") (pinfunction "2_8") (pintype "passive"))
    )
    (net (code "81") (name "Net-(IR3B-2)") (class "Default")
      (node (ref "IL2") (pin "C") (pinfunction "C_C") (pintype "passive"))
      (node (ref "IR3") (pin "7") (pinfunction "2_7") (pintype "passive"))
    )
    (net (code "82") (name "Net-(IR3C-2)") (class "Default")
      (node (ref "IL3") (pin "C") (pinfunction "C_C") (pintype "passive"))
      (node (ref "IR3") (pin "6") (pinfunction "2_6") (pintype "passive"))
    )
    (net (code "83") (name "Net-(IR3D-2)") (class "Default")
      (node (ref "IL4") (pin "C") (pinfunction "C_C") (pintype "passive"))
      (node (ref "IR3") (pin "5") (pinfunction "2_5") (pintype "passive"))
    )
    (net (code "84") (name "Net-(IR4A-2)") (class "Default")
      (node (ref "IL5") (pin "C") (pinfunction "C_C") (pintype "passive"))
      (node (ref "IR4") (pin "8") (pinfunction "2_8") (pintype "passive"))
    )
    (net (code "85") (name "Net-(IR4B-2)") (class "Default")
      (node (ref "IL6") (pin "C") (pinfunction "C_C") (pintype "passive"))
      (node (ref "IR4") (pin "7") (pinfunction "2_7") (pintype "passive"))
    )
    (net (code "86") (name "Net-(IR4C-2)") (class "Default")
      (node (ref "IL7") (pin "C") (pinfunction "C_C") (pintype "passive"))
      (node (ref "IR4") (pin "6") (pinfunction "2_6") (pintype "passive"))
    )
    (net (code "87") (name "Net-(IR4D-2)") (class "Default")
      (node (ref "IL8") (pin "C") (pinfunction "C_C") (pintype "passive"))
      (node (ref "IR4") (pin "5") (pinfunction "2_5") (pintype "passive"))
    )
    (net (code "88") (name "Net-(MC-PB6(XTAL1{slash}TOSC1))") (class "Default")
      (node (ref "MC") (pin "7") (pinfunction "PB6(XTAL1/TOSC1)_7") (pintype "bidirectional"))
      (node (ref "Q1") (pin "1") (pinfunction "1_1") (pintype "passive"))
    )
    (net (code "89") (name "Net-(MC-PB7(XTAL2{slash}TOSC2))") (class "Default")
      (node (ref "MC") (pin "8") (pinfunction "PB7(XTAL2/TOSC2)_8") (pintype "bidirectional"))
      (node (ref "Q1") (pin "3") (pinfunction "3_3") (pintype "passive"))
    )
    (net (code "90") (name "Net-(OD1-PadC)") (class "Default")
      (node (ref "OD1") (pin "C") (pinfunction "C_C") (pintype "passive"))
      (node (ref "OMF") (pin "2") (pinfunction "2_2") (pintype "bidirectional"))
    )
    (net (code "91") (name "Net-(OK3A-A)") (class "Default")
      (node (ref "OK3") (pin "1") (pinfunction "A_1") (pintype "passive"))
      (node (ref "OR1") (pin "4") (pinfunction "1_4") (pintype "passive"))
    )
    (net (code "92") (name "Net-(OK3A-COL)") (class "Default")
      (node (ref "OK3") (pin "16") (pinfunction "COL_16") (pintype "passive"))
      (node (ref "OR3") (pin "1") (pinfunction "1_1") (pintype "passive"))
    )
    (net (code "93") (name "Net-(OK3B-A)") (class "Default")
      (node (ref "OK3") (pin "3") (pinfunction "A_3") (pintype "passive"))
      (node (ref "OR1") (pin "3") (pinfunction "1_3") (pintype "passive"))
    )
    (net (code "94") (name "Net-(OK3B-COL)") (class "Default")
      (node (ref "OK3") (pin "14") (pinfunction "COL_14") (pintype "passive"))
      (node (ref "OR3") (pin "2") (pinfunction "1_2") (pintype "passive"))
    )
    (net (code "95") (name "Net-(OK3C-A)") (class "Default")
      (node (ref "OK3") (pin "5") (pinfunction "A_5") (pintype "passive"))
      (node (ref "OR1") (pin "2") (pinfunction "1_2") (pintype "passive"))
    )
    (net (code "96") (name "Net-(OK3C-COL)") (class "Default")
      (node (ref "OK3") (pin "12") (pinfunction "COL_12") (pintype "passive"))
      (node (ref "OR3") (pin "3") (pinfunction "1_3") (pintype "passive"))
    )
    (net (code "97") (name "Net-(OK3D-A)") (class "Default")
      (node (ref "OK3") (pin "7") (pinfunction "A_7") (pintype "passive"))
      (node (ref "OR1") (pin "1") (pinfunction "1_1") (pintype "passive"))
    )
    (net (code "98") (name "Net-(OK3D-COL)") (class "Default")
      (node (ref "OK3") (pin "10") (pinfunction "COL_10") (pintype "passive"))
      (node (ref "OR3") (pin "4") (pinfunction "1_4") (pintype "passive"))
    )
    (net (code "99") (name "Net-(OK4A-A)") (class "Default")
      (node (ref "OK4") (pin "1") (pinfunction "A_1") (pintype "passive"))
      (node (ref "OR4") (pin "4") (pinfunction "1_4") (pintype "passive"))
    )
    (net (code "100") (name "Net-(OK4A-COL)") (class "Default")
      (node (ref "OK4") (pin "16") (pinfunction "COL_16") (pintype "passive"))
      (node (ref "OR5") (pin "1") (pinfunction "1_1") (pintype "passive"))
    )
    (net (code "101") (name "Net-(OK4B-A)") (class "Default")
      (node (ref "OK4") (pin "3") (pinfunction "A_3") (pintype "passive"))
      (node (ref "OR4") (pin "3") (pinfunction "1_3") (pintype "passive"))
    )
    (net (code "102") (name "Net-(OK4B-COL)") (class "Default")
      (node (ref "OK4") (pin "14") (pinfunction "COL_14") (pintype "passive"))
      (node (ref "OR5") (pin "2") (pinfunction "1_2") (pintype "passive"))
    )
    (net (code "103") (name "Net-(OK4C-A)") (class "Default")
      (node (ref "OK4") (pin "5") (pinfunction "A_5") (pintype "passive"))
      (node (ref "OR4") (pin "2") (pinfunction "1_2") (pintype "passive"))
    )
    (net (code "104") (name "Net-(OK4C-COL)") (class "Default")
      (node (ref "OK4") (pin "12") (pinfunction "COL_12") (pintype "passive"))
      (node (ref "OR5") (pin "3") (pinfunction "1_3") (pintype "passive"))
    )
    (net (code "105") (name "Net-(OK4D-A)") (class "Default")
      (node (ref "OK4") (pin "7") (pinfunction "A_7") (pintype "passive"))
      (node (ref "OR4") (pin "1") (pinfunction "1_1") (pintype "passive"))
    )
    (net (code "106") (name "Net-(OK4D-COL)") (class "Default")
      (node (ref "OK4") (pin "10") (pinfunction "COL_10") (pintype "passive"))
      (node (ref "OR5") (pin "4") (pinfunction "1_4") (pintype "passive"))
    )
    (net (code "107") (name "Net-(OL4-PadA)") (class "Default")
      (node (ref "OL4") (pin "A") (pinfunction "A_A") (pintype "passive"))
      (node (ref "OR7") (pin "1") (pinfunction "1_1") (pintype "passive"))
    )
    (net (code "108") (name "Net-(OL8-PadA)") (class "Default")
      (node (ref "OL8") (pin "A") (pinfunction "A_A") (pintype "passive"))
      (node (ref "OR8") (pin "1") (pinfunction "1_1") (pintype "passive"))
    )
    (net (code "109") (name "Net-(OR7B-1)") (class "Default")
      (node (ref "OL3") (pin "A") (pinfunction "A_A") (pintype "passive"))
      (node (ref "OR7") (pin "2") (pinfunction "1_2") (pintype "passive"))
    )
    (net (code "110") (name "Net-(OR7C-1)") (class "Default")
      (node (ref "OL2") (pin "A") (pinfunction "A_A") (pintype "passive"))
      (node (ref "OR7") (pin "3") (pinfunction "1_3") (pintype "passive"))
    )
    (net (code "111") (name "Net-(OR7D-1)") (class "Default")
      (node (ref "OL1") (pin "A") (pinfunction "A_A") (pintype "passive"))
      (node (ref "OR7") (pin "4") (pinfunction "1_4") (pintype "passive"))
    )
    (net (code "112") (name "Net-(OR8B-1)") (class "Default")
      (node (ref "OL7") (pin "A") (pinfunction "A_A") (pintype "passive"))
      (node (ref "OR8") (pin "2") (pinfunction "1_2") (pintype "passive"))
    )
    (net (code "113") (name "Net-(OR8C-1)") (class "Default")
      (node (ref "OL6") (pin "A") (pinfunction "A_A") (pintype "passive"))
      (node (ref "OR8") (pin "3") (pinfunction "1_3") (pintype "passive"))
    )
    (net (code "114") (name "Net-(OR8D-1)") (class "Default")
      (node (ref "OL5") (pin "A") (pinfunction "A_A") (pintype "passive"))
      (node (ref "OR8") (pin "4") (pinfunction "1_4") (pintype "passive"))
    )
    (net (code "115") (name "Net-(PD1-PadC)") (class "Default")
      (node (ref "PD1") (pin "C") (pinfunction "C_C") (pintype "passive"))
      (node (ref "PF1") (pin "1") (pinfunction "1_1") (pintype "passive"))
    )
    (net (code "116") (name "Net-(PIC33-OUT)") (class "Default")
      (node (ref "PCO") (pin "P$2") (pinfunction "P$2_P$2") (pintype "passive"))
      (node (ref "PD2") (pin "C") (pinfunction "C_C") (pintype "passive"))
      (node (ref "PIC33") (pin "2") (pinfunction "OUT_2") (pintype "output"))
    )
    (net (code "117") (name "Net-(PL-PadA)") (class "Default")
      (node (ref "PL") (pin "A") (pinfunction "A_A") (pintype "passive"))
      (node (ref "PR1") (pin "1") (pinfunction "1_1") (pintype "passive"))
    )
    (net (code "118") (name "Net-(U1-1C)") (class "Default")
      (node (ref "D1") (pin "2") (pinfunction "2_2") (pintype "bidirectional"))
      (node (ref "OF8") (pin "2") (pinfunction "2_2") (pintype "bidirectional"))
      (node (ref "U1") (pin "18") (pinfunction "1C_18") (pintype "output"))
    )
    (net (code "119") (name "Net-(U1-2C)") (class "Default")
      (node (ref "D1") (pin "1") (pinfunction "1_1") (pintype "bidirectional"))
      (node (ref "OF7") (pin "2") (pinfunction "2_2") (pintype "bidirectional"))
      (node (ref "U1") (pin "17") (pinfunction "2C_17") (pintype "output"))
    )
    (net (code "120") (name "Net-(U1-3C)") (class "Default")
      (node (ref "D2") (pin "2") (pinfunction "2_2") (pintype "bidirectional"))
      (node (ref "OF6") (pin "2") (pinfunction "2_2") (pintype "bidirectional"))
      (node (ref "U1") (pin "16") (pinfunction "3C_16") (pintype "output"))
    )
    (net (code "121") (name "Net-(U1-4C)") (class "Default")
      (node (ref "D2") (pin "1") (pinfunction "1_1") (pintype "bidirectional"))
      (node (ref "OF5") (pin "2") (pinfunction "2_2") (pintype "bidirectional"))
      (node (ref "U1") (pin "15") (pinfunction "4C_15") (pintype "output"))
    )
    (net (code "122") (name "Net-(U1-5C)") (class "Default")
      (node (ref "D3") (pin "2") (pinfunction "2_2") (pintype "bidirectional"))
      (node (ref "OF4") (pin "2") (pinfunction "2_2") (pintype "bidirectional"))
      (node (ref "U1") (pin "14") (pinfunction "5C_14") (pintype "output"))
    )
    (net (code "123") (name "Net-(U1-6C)") (class "Default")
      (node (ref "D3") (pin "1") (pinfunction "1_1") (pintype "bidirectional"))
      (node (ref "OF3") (pin "2") (pinfunction "2_2") (pintype "bidirectional"))
      (node (ref "U1") (pin "13") (pinfunction "6C_13") (pintype "output"))
    )
    (net (code "124") (name "Net-(U1-7C)") (class "Default")
      (node (ref "D4") (pin "2") (pinfunction "2_2") (pintype "bidirectional"))
      (node (ref "OF2") (pin "2") (pinfunction "2_2") (pintype "bidirectional"))
      (node (ref "U1") (pin "12") (pinfunction "7C_12") (pintype "output"))
    )
    (net (code "125") (name "Net-(U1-8C)") (class "Default")
      (node (ref "D4") (pin "1") (pinfunction "1_1") (pintype "bidirectional"))
      (node (ref "OF1") (pin "2") (pinfunction "2_2") (pintype "bidirectional"))
      (node (ref "U1") (pin "11") (pinfunction "8C_11") (pintype "output"))
    )
    (net (code "126") (name "Net-(XI1B-SK)") (class "Default")
      (node (ref "IIR1") (pin "1") (pinfunction "1_1") (pintype "passive"))
      (node (ref "XI1") (pin "2") (pinfunction "SK_2") (pintype "passive"))
    )
    (net (code "127") (name "Net-(XI2B-SK)") (class "Default")
      (node (ref "IIR2") (pin "1") (pinfunction "1_1") (pintype "passive"))
      (node (ref "XI2") (pin "2") (pinfunction "SK_2") (pintype "passive"))
    )
    (net (code "128") (name "Net-(XOA-SK)") (class "Default")
      (node (ref "OD1") (pin "A") (pinfunction "A_A") (pintype "passive"))
      (node (ref "XO") (pin "1") (pinfunction "SK_1") (pintype "passive"))
    )
    (net (code "129") (name "Net-(XOB-SK)") (class "Default")
      (node (ref "OF8") (pin "1") (pinfunction "1_1") (pintype "bidirectional"))
      (node (ref "XO") (pin "10") (pinfunction "SK_10") (pintype "passive"))
    )
    (net (code "130") (name "Net-(XOD-SK)") (class "Default")
      (node (ref "OF1") (pin "1") (pinfunction "1_1") (pintype "bidirectional"))
      (node (ref "XO") (pin "3") (pinfunction "SK_3") (pintype "passive"))
    )
    (net (code "131") (name "Net-(XOE-SK)") (class "Default")
      (node (ref "OF2") (pin "1") (pinfunction "1_1") (pintype "bidirectional"))
      (node (ref "XO") (pin "4") (pinfunction "SK_4") (pintype "passive"))
    )
    (net (code "132") (name "Net-(XOF-SK)") (class "Default")
      (node (ref "OF3") (pin "1") (pinfunction "1_1") (pintype "bidirectional"))
      (node (ref "XO") (pin "5") (pinfunction "SK_5") (pintype "passive"))
    )
    (net (code "133") (name "Net-(XOG-SK)") (class "Default")
      (node (ref "OF4") (pin "1") (pinfunction "1_1") (pintype "bidirectional"))
      (node (ref "XO") (pin "6") (pinfunction "SK_6") (pintype "passive"))
    )
    (net (code "134") (name "Net-(XOH-SK)") (class "Default")
      (node (ref "OF5") (pin "1") (pinfunction "1_1") (pintype "bidirectional"))
      (node (ref "XO") (pin "7") (pinfunction "SK_7") (pintype "passive"))
    )
    (net (code "135") (name "Net-(XOI-SK)") (class "Default")
      (node (ref "OF6") (pin "1") (pinfunction "1_1") (pintype "bidirectional"))
      (node (ref "XO") (pin "8") (pinfunction "SK_8") (pintype "passive"))
    )
    (net (code "136") (name "Net-(XOJ-SK)") (class "Default")
      (node (ref "OF7") (pin "1") (pinfunction "1_1") (pintype "bidirectional"))
      (node (ref "XO") (pin "9") (pinfunction "SK_9") (pintype "passive"))
    )
    (net (code "137") (name "OI1") (class "Default")
      (node (ref "OK3") (pin "15") (pinfunction "EMIT_15") (pintype "passive"))
      (node (ref "OR2") (pin "1") (pinfunction "1_1") (pintype "passive"))
      (node (ref "U1") (pin "8") (pinfunction "8B_8") (pintype "input"))
    )
    (net (code "138") (name "OI2") (class "Default")
      (node (ref "OK3") (pin "13") (pinfunction "EMIT_13") (pintype "passive"))
      (node (ref "OR2") (pin "2") (pinfunction "1_2") (pintype "passive"))
      (node (ref "U1") (pin "7") (pinfunction "7B_7") (pintype "input"))
    )
    (net (code "139") (name "OI3") (class "Default")
      (node (ref "OK3") (pin "11") (pinfunction "EMIT_11") (pintype "passive"))
      (node (ref "OR2") (pin "3") (pinfunction "1_3") (pintype "passive"))
      (node (ref "U1") (pin "6") (pinfunction "6B_6") (pintype "input"))
    )
    (net (code "140") (name "OI4") (class "Default")
      (node (ref "OK3") (pin "9") (pinfunction "EMIT_9") (pintype "passive"))
      (node (ref "OR2") (pin "4") (pinfunction "1_4") (pintype "passive"))
      (node (ref "U1") (pin "5") (pinfunction "5B_5") (pintype "input"))
    )
    (net (code "141") (name "RAW_IV") (class "Default")
      (node (ref "GPIO") (pin "1") (pinfunction "S_1") (pintype "passive"))
      (node (ref "PC1") (pin "+") (pinfunction "+_+") (pintype "passive"))
      (node (ref "PF1") (pin "2") (pinfunction "2_2") (pintype "passive"))
      (node (ref "PIC33") (pin "1") (pinfunction "VIN_1") (pintype "input"))
    )
    (net (code "142") (name "RESET") (class "Default")
      (node (ref "BL") (pin "5") (pinfunction "S_5") (pintype "passive"))
      (node (ref "C2") (pin "1") (pinfunction "1_1") (pintype "passive"))
      (node (ref "MC") (pin "29") (pinfunction "PC6(/RESET)_29") (pintype "bidirectional"))
      (node (ref "R2") (pin "1") (pinfunction "1_1") (pintype "passive"))
      (node (ref "SR") (pin "1") (pinfunction "P_1") (pintype "passive"))
    )
    (net (code "143") (name "RXI") (class "Default")
      (node (ref "MC") (pin "30") (pinfunction "PD0(RXD)_30") (pintype "bidirectional"))
      (node (ref "PP") (pin "4") (pinfunction "S_4") (pintype "passive"))
    )
    (net (code "144") (name "TXO") (class "Default")
      (node (ref "MC") (pin "31") (pinfunction "PD1(TXD)_31") (pintype "bidirectional"))
      (node (ref "PP") (pin "3") (pinfunction "S_3") (pintype "passive"))
    )
    (net (code "145") (name "VDDO") (class "Default")
      (node (ref "D1") (pin "3") (pinfunction "3_3") (pintype "bidirectional"))
      (node (ref "D2") (pin "3") (pinfunction "3_3") (pintype "bidirectional"))
      (node (ref "D3") (pin "3") (pinfunction "3_3") (pintype "bidirectional"))
      (node (ref "D4") (pin "3") (pinfunction "3_3") (pintype "bidirectional"))
      (node (ref "EC6") (pin "+") (pinfunction "+_+") (pintype "passive"))
      (node (ref "OD2") (pin "C") (pinfunction "C_C") (pintype "passive"))
      (node (ref "OMF") (pin "1") (pinfunction "1_1") (pintype "bidirectional"))
      (node (ref "OR3") (pin "5") (pinfunction "2_5") (pintype "passive"))
      (node (ref "OR3") (pin "6") (pinfunction "2_6") (pintype "passive"))
      (node (ref "OR3") (pin "7") (pinfunction "2_7") (pintype "passive"))
      (node (ref "OR3") (pin "8") (pinfunction "2_8") (pintype "passive"))
      (node (ref "OR5") (pin "5") (pinfunction "2_5") (pintype "passive"))
      (node (ref "OR5") (pin "6") (pinfunction "2_6") (pintype "passive"))
      (node (ref "OR5") (pin "7") (pinfunction "2_7") (pintype "passive"))
      (node (ref "OR5") (pin "8") (pinfunction "2_8") (pintype "passive"))
      (node (ref "U1") (pin "10") (pinfunction "COM_10") (pintype "output"))
    )
    (net (code "146") (name "VIN") (class "Default")
      (node (ref "PD1") (pin "A") (pinfunction "A_A") (pintype "passive"))
      (node (ref "PJ1") (pin "VIN0") (pinfunction "PWR_VIN0") (pintype "bidirectional"))
      (node (ref "XV") (pin "2") (pinfunction "SK_2") (pintype "passive"))
    )
    (net (code "147") (name "WFGPIO0") (class "Default")
      (node (ref "GPIO") (pin "13") (pinfunction "S_13") (pintype "passive"))
      (node (ref "WIFI") (pin "GPIO0") (pinfunction "GPIO0_GPIO0") (pintype "bidirectional"))
    )
    (net (code "148") (name "WFGPIO2") (class "Default")
      (node (ref "GPIO") (pin "14") (pinfunction "S_14") (pintype "passive"))
      (node (ref "WIFI") (pin "GPIO2") (pinfunction "GPIO2_GPIO2") (pintype "bidirectional"))
    )
    (net (code "149") (name "unconnected-(ENC-CLKOUT-Pad3)") (class "Default")
      (node (ref "ENC") (pin "3") (pinfunction "CLKOUT_3") (pintype "output"))
    )
    (net (code "150") (name "unconnected-(ENC-WOL-Pad5)") (class "Default")
      (node (ref "ENC") (pin "5") (pinfunction "WOL_5") (pintype "output"))
    )
    (net (code "151") (name "unconnected-(IC1-INTA-Pad20)") (class "Default")
      (node (ref "IC1") (pin "20") (pinfunction "INTA_20") (pintype "output"))
    )
    (net (code "152") (name "unconnected-(PJ1-GND-PadP$4)") (class "Default")
      (node (ref "PJ1") (pin "P$4") (pinfunction "GND_P$4") (pintype "bidirectional"))
    )
    (net (code "153") (name "unconnected-(SHT-PadALERT)") (class "Default")
      (node (ref "SHT") (pin "ALERT") (pinfunction "ALERT_ALERT") (pintype "bidirectional"))
    )
    (net (code "154") (name "unconnected-(SHT-PadRESET)") (class "Default")
      (node (ref "SHT") (pin "RESET") (pinfunction "RESET_RESET") (pintype "bidirectional"))
    )
    (net (code "155") (name "unconnected-(U$2-PadNC)") (class "Default")
      (node (ref "U$2") (pin "NC") (pinfunction "NC_NC") (pintype "bidirectional"))
    )
    (net (code "156") (name "unconnected-(WIFI-PadRST)") (class "Default")
      (node (ref "WIFI") (pin "RST") (pinfunction "RST_RST") (pintype "bidirectional"))
    )
  )
)
